# mx8m_phy.net
KiCad netlist of a schematic drawn in Altium Designer
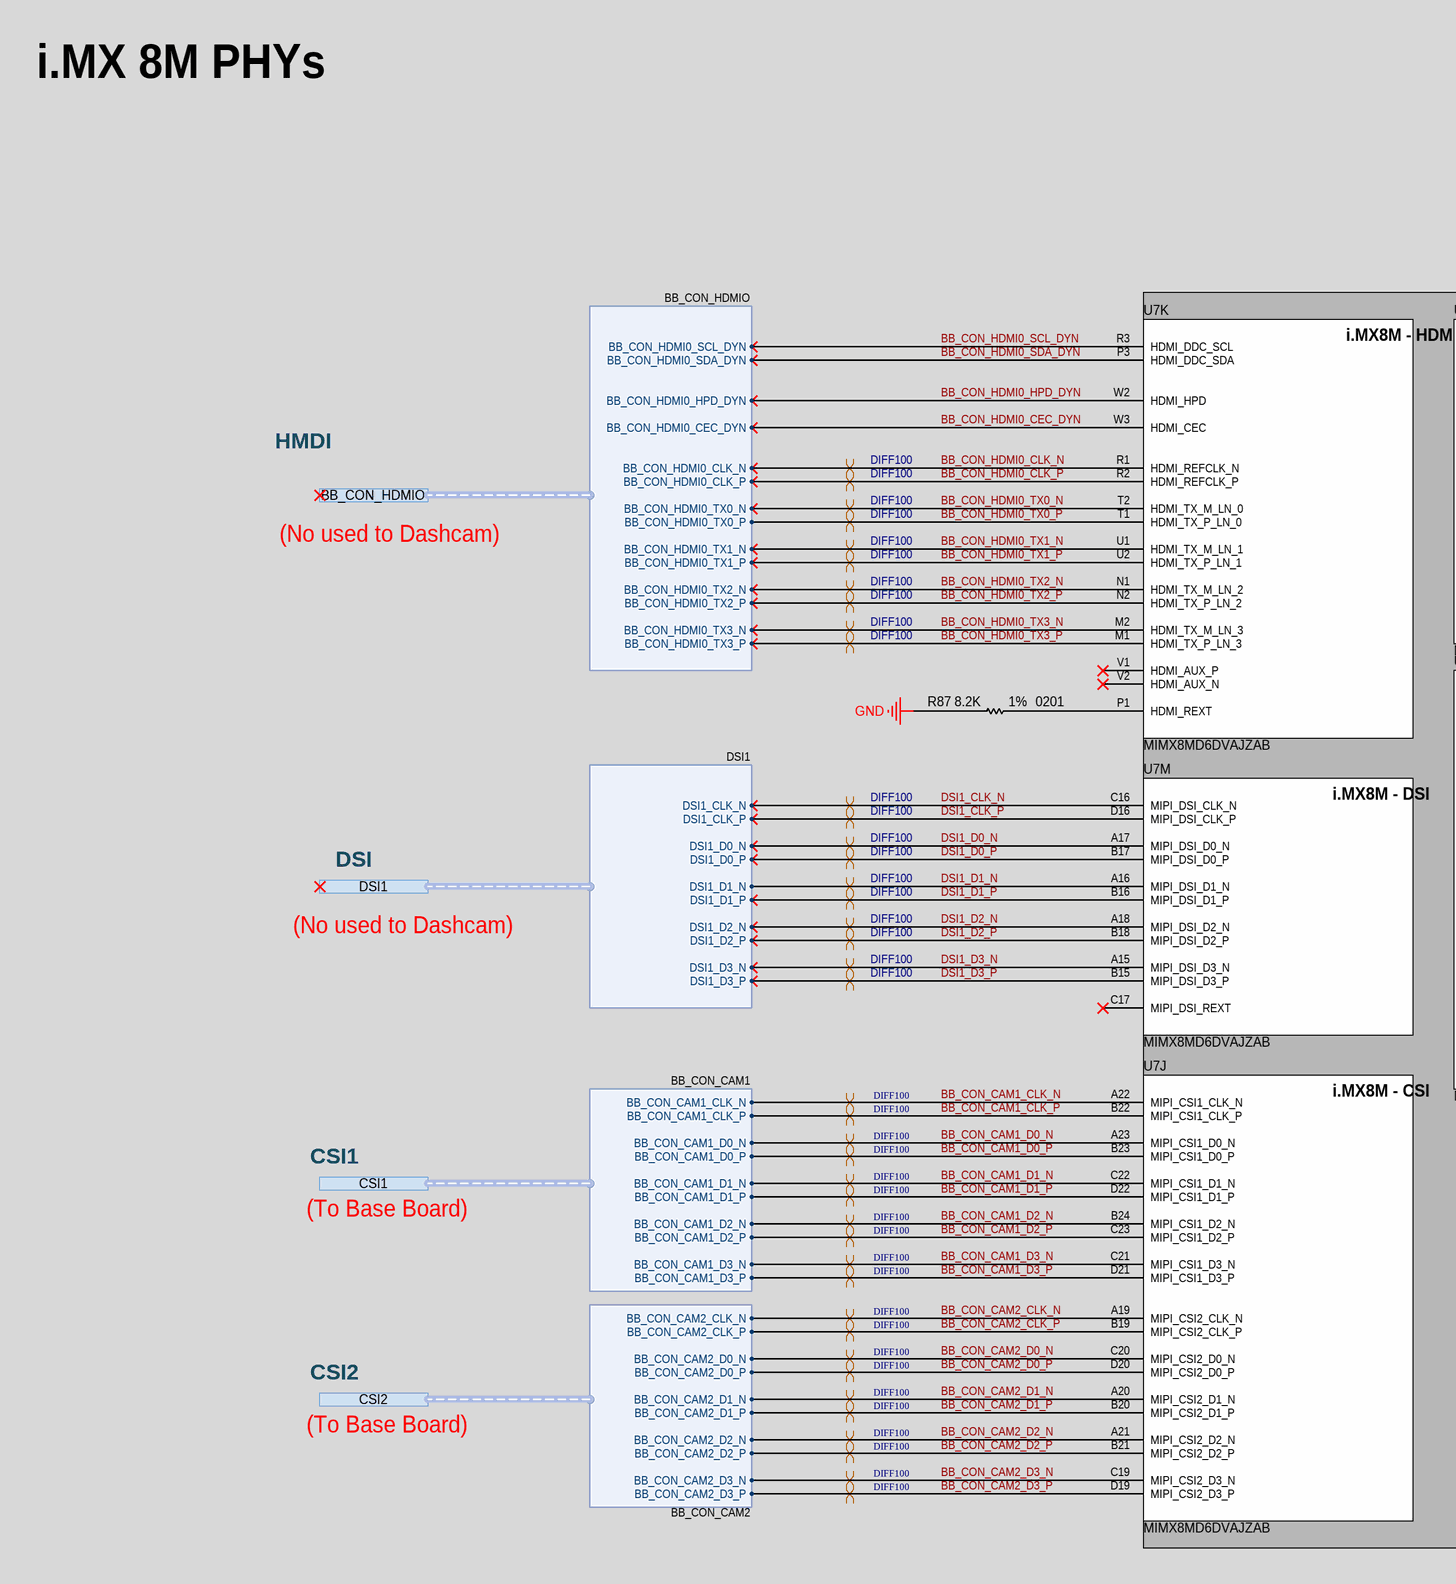
[diagram p0: mx8m_phy.SchDoc, left]
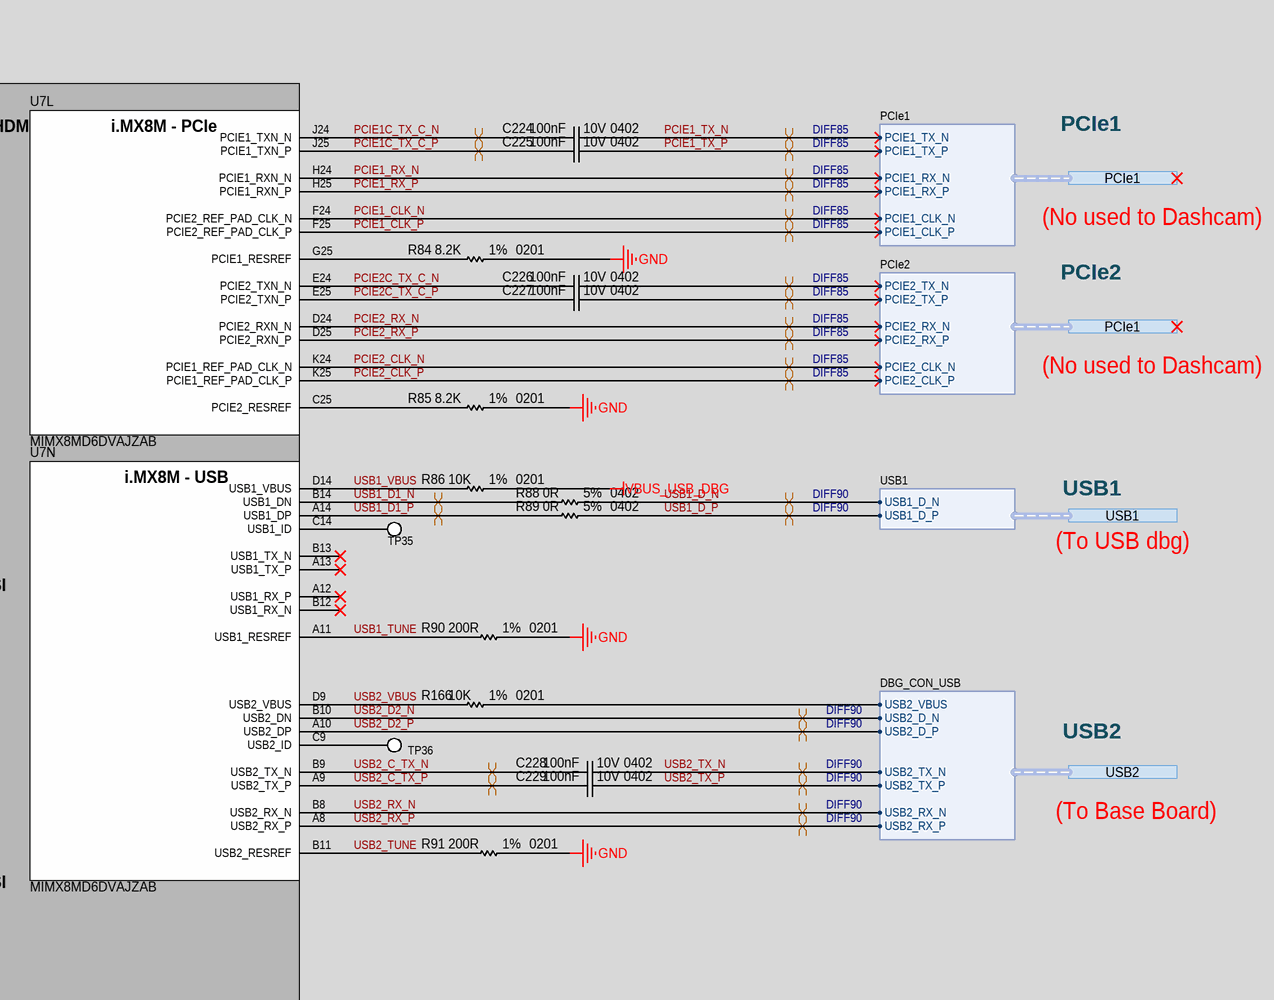
[diagram p1: mx8m_phy.SchDoc, right]

(export (version "E")
  (design (tool "Eeschema 10.0.6"))
  (components
    (comp (ref "C224")
      (value "GRM155R61A104KA01D")
      (footprint "CAP_0402_CAPC1005X05N")
      (description "Multilayer Ceramic Capacitor, 0.1 uF, 10 V, ± 10%, X5R, 0402 [1005 Metric]")
      (fields
        (field (name "MANUFACTURER") "Murata")
        (field (name "TOLERANCE") "10%")
        (field (name "CASE CODE (IMPERIAL)") "0402")
        (field (name "VOLTAGE RATING (DC)") "10V")
        (field (name "CAPACITANCE") "100nF")
      )
      (libsource (lib "Electronic Devices_LIB") (part "CAP_100nF_10V_X5R_0402"))
    )
    (comp (ref "C225")
      (value "GRM155R61A104KA01D")
      (footprint "CAP_0402_CAPC1005X05N")
      (description "Multilayer Ceramic Capacitor, 0.1 uF, 10 V, ± 10%, X5R, 0402 [1005 Metric]")
      (fields
        (field (name "MANUFACTURER") "Murata")
        (field (name "TOLERANCE") "10%")
        (field (name "CASE CODE (IMPERIAL)") "0402")
        (field (name "VOLTAGE RATING (DC)") "10V")
        (field (name "CAPACITANCE") "100nF")
      )
      (libsource (lib "Electronic Devices_LIB") (part "CAP_100nF_10V_X5R_0402"))
    )
    (comp (ref "C226")
      (value "GRM155R61A104KA01D")
      (footprint "CAP_0402_CAPC1005X05N")
      (description "Multilayer Ceramic Capacitor, 0.1 uF, 10 V, ± 10%, X5R, 0402 [1005 Metric]")
      (fields
        (field (name "MANUFACTURER") "Murata")
        (field (name "TOLERANCE") "10%")
        (field (name "CASE CODE (IMPERIAL)") "0402")
        (field (name "VOLTAGE RATING (DC)") "10V")
        (field (name "CAPACITANCE") "100nF")
      )
      (libsource (lib "Electronic Devices_LIB") (part "CAP_100nF_10V_X5R_0402"))
    )
    (comp (ref "C227")
      (value "GRM155R61A104KA01D")
      (footprint "CAP_0402_CAPC1005X05N")
      (description "Multilayer Ceramic Capacitor, 0.1 uF, 10 V, ± 10%, X5R, 0402 [1005 Metric]")
      (fields
        (field (name "MANUFACTURER") "Murata")
        (field (name "TOLERANCE") "10%")
        (field (name "CASE CODE (IMPERIAL)") "0402")
        (field (name "VOLTAGE RATING (DC)") "10V")
        (field (name "CAPACITANCE") "100nF")
      )
      (libsource (lib "Electronic Devices_LIB") (part "CAP_100nF_10V_X5R_0402"))
    )
    (comp (ref "C228")
      (value "GRM155R61A104KA01D")
      (footprint "CAP_0402_CAPC1005X05N")
      (description "Multilayer Ceramic Capacitor, 0.1 uF, 10 V, ± 10%, X5R, 0402 [1005 Metric]")
      (fields
        (field (name "MANUFACTURER") "Murata")
        (field (name "TOLERANCE") "10%")
        (field (name "CASE CODE (IMPERIAL)") "0402")
        (field (name "VOLTAGE RATING (DC)") "10V")
        (field (name "CAPACITANCE") "100nF")
      )
      (libsource (lib "Electronic Devices_LIB") (part "CAP_100nF_10V_X5R_0402"))
    )
    (comp (ref "C229")
      (value "GRM155R61A104KA01D")
      (footprint "CAP_0402_CAPC1005X05N")
      (description "Multilayer Ceramic Capacitor, 0.1 uF, 10 V, ± 10%, X5R, 0402 [1005 Metric]")
      (fields
        (field (name "MANUFACTURER") "Murata")
        (field (name "TOLERANCE") "10%")
        (field (name "CASE CODE (IMPERIAL)") "0402")
        (field (name "VOLTAGE RATING (DC)") "10V")
        (field (name "CAPACITANCE") "100nF")
      )
      (libsource (lib "Electronic Devices_LIB") (part "CAP_100nF_10V_X5R_0402"))
    )
    (comp (ref "R84")
      (value "RC0201FR-078K2L")
      (footprint "RES_0201_RESC0603X02N")
      (description "Res Thick Film 0201 8.2K Ohm 1% 1/20W ±200ppm/°C Molded SMD Paper T/R")
      (fields
        (field (name "MANUFACTURER") "Yageo")
        (field (name "TOLERANCE") "1%")
        (field (name "RESISTANCE") "8.2K")
        (field (name "CASE/PACKAGE") "0201")
      )
      (libsource (lib "Electronic Devices_LIB") (part "RES_8.2K_1%_50mW_0201"))
    )
    (comp (ref "R85")
      (value "RC0201FR-078K2L")
      (footprint "RES_0201_RESC0603X02N")
      (description "Res Thick Film 0201 8.2K Ohm 1% 1/20W ±200ppm/°C Molded SMD Paper T/R")
      (fields
        (field (name "MANUFACTURER") "Yageo")
        (field (name "TOLERANCE") "1%")
        (field (name "RESISTANCE") "8.2K")
        (field (name "CASE/PACKAGE") "0201")
      )
      (libsource (lib "Electronic Devices_LIB") (part "RES_8.2K_1%_50mW_0201"))
    )
    (comp (ref "R86")
      (value "RC0201FR-0710KL")
      (footprint "RES_0201_RESC0603X02N")
      (description "SMD Chip Resistor, 10 kOhm, ± 1%, 50 mW, 0201 [0603 Metric], Thick Film, General Purpose")
      (fields
        (field (name "MANUFACTURER") "Yageo")
        (field (name "TOLERANCE") "1%")
        (field (name "RESISTANCE") "10K")
        (field (name "CASE CODE (IMPERIAL)") "0201")
      )
      (libsource (lib "Electronic Devices_LIB") (part "RES_10K_1/12W_1%_0201"))
    )
    (comp (ref "R87")
      (value "RC0201FR-078K2L")
      (footprint "RES_0201_RESC0603X02N")
      (description "Res Thick Film 0201 8.2K Ohm 1% 1/20W ±200ppm/°C Molded SMD Paper T/R")
      (fields
        (field (name "MANUFACTURER") "Yageo")
        (field (name "TOLERANCE") "1%")
        (field (name "RESISTANCE") "8.2K")
        (field (name "CASE/PACKAGE") "0201")
      )
      (libsource (lib "Electronic Devices_LIB") (part "RES_8.2K_1%_50mW_0201"))
    )
    (comp (ref "R88")
      (value "ERJ-2GE0R00X")
      (footprint "RES_0402_RESC1005X04N")
      (description "SMD Chip Resistor, Jumper, 0 ohm, 100 mW, 0402 [1005 Metric], Thick Film, General Purpose")
      (fields
        (field (name "MANUFACTURER") "Panasonic")
        (field (name "CASE CODE (IMPERIAL)") "0402")
        (field (name "TOLERANCE") "5%")
        (field (name "RESISTANCE") "0R")
      )
      (libsource (lib "Electronic Devices_LIB") (part "RES_0R_5%_100mW_0402"))
    )
    (comp (ref "R89")
      (value "ERJ-2GE0R00X")
      (footprint "RES_0402_RESC1005X04N")
      (description "SMD Chip Resistor, Jumper, 0 ohm, 100 mW, 0402 [1005 Metric], Thick Film, General Purpose")
      (fields
        (field (name "MANUFACTURER") "Panasonic")
        (field (name "CASE CODE (IMPERIAL)") "0402")
        (field (name "TOLERANCE") "5%")
        (field (name "RESISTANCE") "0R")
      )
      (libsource (lib "Electronic Devices_LIB") (part "RES_0R_5%_100mW_0402"))
    )
    (comp (ref "R90")
      (value "RC0201FR-07200RL")
      (footprint "RES_0201_RESC0603X02N")
      (description "SMD Chip Resistor, 200 Ohm, ± 1%, 50 mW, 0201 [0603 Metric], Thick Film, General Purpose")
      (fields
        (field (name "MANUFACTURER") "Yageo")
        (field (name "TOLERANCE") "1%")
        (field (name "RESISTANCE") "200R")
        (field (name "CASE/PACKAGE") "0201")
      )
      (libsource (lib "Electronic Devices_LIB") (part "RES_200R_1%_50mW_0201"))
    )
    (comp (ref "R91")
      (value "RC0201FR-07200RL")
      (footprint "RES_0201_RESC0603X02N")
      (description "SMD Chip Resistor, 200 Ohm, ± 1%, 50 mW, 0201 [0603 Metric], Thick Film, General Purpose")
      (fields
        (field (name "MANUFACTURER") "Yageo")
        (field (name "TOLERANCE") "1%")
        (field (name "RESISTANCE") "200R")
        (field (name "CASE/PACKAGE") "0201")
      )
      (libsource (lib "Electronic Devices_LIB") (part "RES_200R_1%_50mW_0201"))
    )
    (comp (ref "R166")
      (value "RC0201FR-0710KL")
      (footprint "RES_0201_RESC0603X02N")
      (description "SMD Chip Resistor, 10 kOhm, ± 1%, 50 mW, 0201 [0603 Metric], Thick Film, General Purpose")
      (fields
        (field (name "MANUFACTURER") "Yageo")
        (field (name "TOLERANCE") "1%")
        (field (name "RESISTANCE") "10K")
        (field (name "CASE CODE (IMPERIAL)") "0201")
      )
      (libsource (lib "Electronic Devices_LIB") (part "RES_10K_1/12W_1%_0201"))
    )
    (comp (ref "TP35")
      (value "NO COMPONENT")
      (footprint "TP_PAD_1.6MM_SMD_ROUND")
      (description "Test Point, SMD pad, round, 1.5mm, 1.6mm, 3mm diameter")
      (libsource (lib "Electronic Devices_LIB") (part "TP_PAD_SMD_Round"))
    )
    (comp (ref "TP36")
      (value "NO COMPONENT")
      (footprint "TP_PAD_1.6MM_SMD_ROUND")
      (description "Test Point, SMD pad, round, 1.5mm, 1.6mm, 3mm diameter")
      (libsource (lib "Electronic Devices_LIB") (part "TP_PAD_SMD_Round"))
    )
    (comp (ref "U7")
      (value "MIMX8MD6DVAJZAB")
      (footprint "IC_MPU_BGA621C65P25X25_1700X1700X218")
      (fields (field (name "MANUFACTURER") "NXP Semiconductors"))
      (libsource (lib "Electronic Devices_LIB") (part "IC_MPU_ARM_1.5GHZ_MIMX8MD6DVAJZAB"))
    )
  )
  (nets
    (net (code "9") (name "/BB_CON_CAM1_CLK_N") (class "Default")
      (node (ref "U7") (pin "A22") (pinfunction "MIPI_CSI1_CLK_N_A22") (pintype "passive"))
    )
    (net (code "10") (name "/BB_CON_CAM1_CLK_P") (class "Default")
      (node (ref "U7") (pin "B22") (pinfunction "MIPI_CSI1_CLK_P_B22") (pintype "passive"))
    )
    (net (code "11") (name "/BB_CON_CAM1_D0_N") (class "Default")
      (node (ref "U7") (pin "A23") (pinfunction "MIPI_CSI1_D0_N_A23") (pintype "passive"))
    )
    (net (code "12") (name "/BB_CON_CAM1_D0_P") (class "Default")
      (node (ref "U7") (pin "B23") (pinfunction "MIPI_CSI1_D0_P_B23") (pintype "passive"))
    )
    (net (code "13") (name "/BB_CON_CAM1_D1_N") (class "Default")
      (node (ref "U7") (pin "C22") (pinfunction "MIPI_CSI1_D1_N_C22") (pintype "passive"))
    )
    (net (code "14") (name "/BB_CON_CAM1_D1_P") (class "Default")
      (node (ref "U7") (pin "D22") (pinfunction "MIPI_CSI1_D1_P_D22") (pintype "passive"))
    )
    (net (code "15") (name "/BB_CON_CAM1_D2_N") (class "Default")
      (node (ref "U7") (pin "B24") (pinfunction "MIPI_CSI1_D2_N_B24") (pintype "passive"))
    )
    (net (code "16") (name "/BB_CON_CAM1_D2_P") (class "Default")
      (node (ref "U7") (pin "C23") (pinfunction "MIPI_CSI1_D2_P_C23") (pintype "passive"))
    )
    (net (code "17") (name "/BB_CON_CAM1_D3_N") (class "Default")
      (node (ref "U7") (pin "C21") (pinfunction "MIPI_CSI1_D3_N_C21") (pintype "passive"))
    )
    (net (code "18") (name "/BB_CON_CAM1_D3_P") (class "Default")
      (node (ref "U7") (pin "D21") (pinfunction "MIPI_CSI1_D3_P_D21") (pintype "passive"))
    )
    (net (code "19") (name "/BB_CON_CAM2_CLK_N") (class "Default")
      (node (ref "U7") (pin "A19") (pinfunction "MIPI_CSI2_CLK_N_A19") (pintype "passive"))
    )
    (net (code "20") (name "/BB_CON_CAM2_CLK_P") (class "Default")
      (node (ref "U7") (pin "B19") (pinfunction "MIPI_CSI2_CLK_P_B19") (pintype "passive"))
    )
    (net (code "21") (name "/BB_CON_CAM2_D0_N") (class "Default")
      (node (ref "U7") (pin "C20") (pinfunction "MIPI_CSI2_D0_N_C20") (pintype "passive"))
    )
    (net (code "22") (name "/BB_CON_CAM2_D0_P") (class "Default")
      (node (ref "U7") (pin "D20") (pinfunction "MIPI_CSI2_D0_P_D20") (pintype "passive"))
    )
    (net (code "23") (name "/BB_CON_CAM2_D1_N") (class "Default")
      (node (ref "U7") (pin "A20") (pinfunction "MIPI_CSI2_D1_N_A20") (pintype "passive"))
    )
    (net (code "24") (name "/BB_CON_CAM2_D1_P") (class "Default")
      (node (ref "U7") (pin "B20") (pinfunction "MIPI_CSI2_D1_P_B20") (pintype "passive"))
    )
    (net (code "25") (name "/BB_CON_CAM2_D2_N") (class "Default")
      (node (ref "U7") (pin "A21") (pinfunction "MIPI_CSI2_D2_N_A21") (pintype "passive"))
    )
    (net (code "26") (name "/BB_CON_CAM2_D2_P") (class "Default")
      (node (ref "U7") (pin "B21") (pinfunction "MIPI_CSI2_D2_P_B21") (pintype "passive"))
    )
    (net (code "27") (name "/BB_CON_CAM2_D3_N") (class "Default")
      (node (ref "U7") (pin "C19") (pinfunction "MIPI_CSI2_D3_N_C19") (pintype "passive"))
    )
    (net (code "28") (name "/BB_CON_CAM2_D3_P") (class "Default")
      (node (ref "U7") (pin "D19") (pinfunction "MIPI_CSI2_D3_P_D19") (pintype "passive"))
    )
    (net (code "29") (name "/BB_CON_HDMI0_CEC_DYN") (class "Default")
      (node (ref "U7") (pin "W3") (pinfunction "HDMI_CEC_W3") (pintype "passive+no_connect"))
    )
    (net (code "30") (name "/BB_CON_HDMI0_CLK_N") (class "Default")
      (node (ref "U7") (pin "R1") (pinfunction "HDMI_REFCLK_N_R1") (pintype "passive+no_connect"))
    )
    (net (code "31") (name "/BB_CON_HDMI0_CLK_P") (class "Default")
      (node (ref "U7") (pin "R2") (pinfunction "HDMI_REFCLK_P_R2") (pintype "passive+no_connect"))
    )
    (net (code "32") (name "/BB_CON_HDMI0_HPD_DYN") (class "Default")
      (node (ref "U7") (pin "W2") (pinfunction "HDMI_HPD_W2") (pintype "passive+no_connect"))
    )
    (net (code "33") (name "/BB_CON_HDMI0_SCL_DYN") (class "Default")
      (node (ref "U7") (pin "R3") (pinfunction "HDMI_DDC_SCL_R3") (pintype "passive+no_connect"))
    )
    (net (code "34") (name "/BB_CON_HDMI0_SDA_DYN") (class "Default")
      (node (ref "U7") (pin "P3") (pinfunction "HDMI_DDC_SDA_P3") (pintype "passive+no_connect"))
    )
    (net (code "35") (name "/BB_CON_HDMI0_TX0_N") (class "Default")
      (node (ref "U7") (pin "T2") (pinfunction "HDMI_TX_M_LN_0_T2") (pintype "passive+no_connect"))
    )
    (net (code "36") (name "/BB_CON_HDMI0_TX0_P") (class "Default")
      (node (ref "U7") (pin "T1") (pinfunction "HDMI_TX_P_LN_0_T1") (pintype "passive"))
    )
    (net (code "37") (name "/BB_CON_HDMI0_TX1_N") (class "Default")
      (node (ref "U7") (pin "U1") (pinfunction "HDMI_TX_M_LN_1_U1") (pintype "passive+no_connect"))
    )
    (net (code "38") (name "/BB_CON_HDMI0_TX1_P") (class "Default")
      (node (ref "U7") (pin "U2") (pinfunction "HDMI_TX_P_LN_1_U2") (pintype "passive+no_connect"))
    )
    (net (code "39") (name "/BB_CON_HDMI0_TX2_N") (class "Default")
      (node (ref "U7") (pin "N1") (pinfunction "HDMI_TX_M_LN_2_N1") (pintype "passive+no_connect"))
    )
    (net (code "40") (name "/BB_CON_HDMI0_TX2_P") (class "Default")
      (node (ref "U7") (pin "N2") (pinfunction "HDMI_TX_P_LN_2_N2") (pintype "passive+no_connect"))
    )
    (net (code "41") (name "/BB_CON_HDMI0_TX3_N") (class "Default")
      (node (ref "U7") (pin "M2") (pinfunction "HDMI_TX_M_LN_3_M2") (pintype "passive+no_connect"))
    )
    (net (code "42") (name "/BB_CON_HDMI0_TX3_P") (class "Default")
      (node (ref "U7") (pin "M1") (pinfunction "HDMI_TX_P_LN_3_M1") (pintype "passive+no_connect"))
    )
    (net (code "43") (name "/DSI1_CLK_N") (class "Default")
      (node (ref "U7") (pin "C16") (pinfunction "MIPI_DSI_CLK_N_C16") (pintype "passive+no_connect"))
    )
    (net (code "44") (name "/DSI1_CLK_P") (class "Default")
      (node (ref "U7") (pin "D16") (pinfunction "MIPI_DSI_CLK_P_D16") (pintype "passive+no_connect"))
    )
    (net (code "45") (name "/DSI1_D0_N") (class "Default")
      (node (ref "U7") (pin "A17") (pinfunction "MIPI_DSI_D0_N_A17") (pintype "passive+no_connect"))
    )
    (net (code "46") (name "/DSI1_D0_P") (class "Default")
      (node (ref "U7") (pin "B17") (pinfunction "MIPI_DSI_D0_P_B17") (pintype "passive+no_connect"))
    )
    (net (code "47") (name "/DSI1_D1_N") (class "Default")
      (node (ref "U7") (pin "A16") (pinfunction "MIPI_DSI_D1_N_A16") (pintype "passive"))
    )
    (net (code "48") (name "/DSI1_D1_P") (class "Default")
      (node (ref "U7") (pin "B16") (pinfunction "MIPI_DSI_D1_P_B16") (pintype "passive+no_connect"))
    )
    (net (code "49") (name "/DSI1_D2_N") (class "Default")
      (node (ref "U7") (pin "A18") (pinfunction "MIPI_DSI_D2_N_A18") (pintype "passive+no_connect"))
    )
    (net (code "50") (name "/DSI1_D2_P") (class "Default")
      (node (ref "U7") (pin "B18") (pinfunction "MIPI_DSI_D2_P_B18") (pintype "passive+no_connect"))
    )
    (net (code "51") (name "/DSI1_D3_N") (class "Default")
      (node (ref "U7") (pin "A15") (pinfunction "MIPI_DSI_D3_N_A15") (pintype "passive+no_connect"))
    )
    (net (code "52") (name "/DSI1_D3_P") (class "Default")
      (node (ref "U7") (pin "B15") (pinfunction "MIPI_DSI_D3_P_B15") (pintype "passive+no_connect"))
    )
    (net (code "53") (name "/PCIE1C_TX_C_N") (class "Default")
      (node (ref "C224") (pin "1") (pinfunction "1_1") (pintype "passive"))
      (node (ref "U7") (pin "J24") (pinfunction "PCIE1_TXN_N_J24") (pintype "passive"))
    )
    (net (code "54") (name "/PCIE1C_TX_C_P") (class "Default")
      (node (ref "C225") (pin "1") (pinfunction "1_1") (pintype "passive"))
      (node (ref "U7") (pin "J25") (pinfunction "PCIE1_TXN_P_J25") (pintype "passive"))
    )
    (net (code "55") (name "/PCIE1_CLK_N") (class "Default")
      (node (ref "U7") (pin "F24") (pinfunction "PCIE2_REF_PAD_CLK_N_F24") (pintype "passive+no_connect"))
    )
    (net (code "56") (name "/PCIE1_CLK_P") (class "Default")
      (node (ref "U7") (pin "F25") (pinfunction "PCIE2_REF_PAD_CLK_P_F25") (pintype "passive+no_connect"))
    )
    (net (code "57") (name "/PCIE1_RX_N") (class "Default")
      (node (ref "U7") (pin "H24") (pinfunction "PCIE1_RXN_N_H24") (pintype "passive+no_connect"))
    )
    (net (code "58") (name "/PCIE1_RX_P") (class "Default")
      (node (ref "U7") (pin "H25") (pinfunction "PCIE1_RXN_P_H25") (pintype "passive+no_connect"))
    )
    (net (code "59") (name "/PCIE1_TX_N") (class "Default")
      (node (ref "C224") (pin "2") (pinfunction "2_2") (pintype "passive+no_connect"))
    )
    (net (code "60") (name "/PCIE1_TX_P") (class "Default")
      (node (ref "C225") (pin "2") (pinfunction "2_2") (pintype "passive+no_connect"))
    )
    (net (code "61") (name "/PCIE2C_TX_C_N") (class "Default")
      (node (ref "C226") (pin "1") (pinfunction "1_1") (pintype "passive"))
      (node (ref "U7") (pin "E24") (pinfunction "PCIE2_TXN_N_E24") (pintype "passive"))
    )
    (net (code "62") (name "/PCIE2C_TX_C_P") (class "Default")
      (node (ref "C227") (pin "1") (pinfunction "1_1") (pintype "passive"))
      (node (ref "U7") (pin "E25") (pinfunction "PCIE2_TXN_P_E25") (pintype "passive"))
    )
    (net (code "63") (name "/PCIE2_CLK_N") (class "Default")
      (node (ref "U7") (pin "K24") (pinfunction "PCIE1_REF_PAD_CLK_N_K24") (pintype "passive+no_connect"))
    )
    (net (code "64") (name "/PCIE2_CLK_P") (class "Default")
      (node (ref "U7") (pin "K25") (pinfunction "PCIE1_REF_PAD_CLK_P_K25") (pintype "passive+no_connect"))
    )
    (net (code "65") (name "/PCIE2_RX_N") (class "Default")
      (node (ref "U7") (pin "D24") (pinfunction "PCIE2_RXN_N_D24") (pintype "passive+no_connect"))
    )
    (net (code "66") (name "/PCIE2_RX_P") (class "Default")
      (node (ref "U7") (pin "D25") (pinfunction "PCIE2_RXN_P_D25") (pintype "passive+no_connect"))
    )
    (net (code "67") (name "/PCIE2_TX_N") (class "Default")
      (node (ref "C226") (pin "2") (pinfunction "2_2") (pintype "passive+no_connect"))
    )
    (net (code "68") (name "/PCIE2_TX_P") (class "Default")
      (node (ref "C227") (pin "2") (pinfunction "2_2") (pintype "passive+no_connect"))
    )
    (net (code "69") (name "/USB1_D1_N") (class "Default")
      (node (ref "R88") (pin "1") (pinfunction "1_1") (pintype "passive"))
      (node (ref "U7") (pin "B14") (pinfunction "USB1_DN_B14") (pintype "passive"))
    )
    (net (code "70") (name "/USB1_D1_P") (class "Default")
      (node (ref "R89") (pin "1") (pinfunction "1_1") (pintype "passive"))
      (node (ref "U7") (pin "A14") (pinfunction "USB1_DP_A14") (pintype "passive"))
    )
    (net (code "71") (name "/USB1_D_N") (class "Default")
      (node (ref "R88") (pin "2") (pinfunction "2_2") (pintype "passive"))
    )
    (net (code "72") (name "/USB1_D_P") (class "Default")
      (node (ref "R89") (pin "2") (pinfunction "2_2") (pintype "passive"))
    )
    (net (code "73") (name "/USB1_TUNE") (class "Default")
      (node (ref "R90") (pin "1") (pinfunction "1_1") (pintype "passive"))
      (node (ref "U7") (pin "A11") (pinfunction "USB1_RESREF_A11") (pintype "passive"))
    )
    (net (code "74") (name "/USB1_VBUS") (class "Default")
      (node (ref "R86") (pin "1") (pinfunction "1_1") (pintype "passive"))
      (node (ref "U7") (pin "D14") (pinfunction "USB1_VBUS_D14") (pintype "passive"))
    )
    (net (code "75") (name "/USB2_C_TX_N") (class "Default")
      (node (ref "C228") (pin "1") (pinfunction "1_1") (pintype "passive"))
      (node (ref "U7") (pin "B9") (pinfunction "USB2_TX_N_B9") (pintype "passive"))
    )
    (net (code "76") (name "/USB2_C_TX_P") (class "Default")
      (node (ref "C229") (pin "1") (pinfunction "1_1") (pintype "passive"))
      (node (ref "U7") (pin "A9") (pinfunction "USB2_TX_P_A9") (pintype "passive"))
    )
    (net (code "77") (name "/USB2_D2_N") (class "Default")
      (node (ref "U7") (pin "B10") (pinfunction "USB2_DN_B10") (pintype "passive"))
    )
    (net (code "78") (name "/USB2_D2_P") (class "Default")
      (node (ref "U7") (pin "A10") (pinfunction "USB2_DP_A10") (pintype "passive"))
    )
    (net (code "79") (name "/USB2_RX_N") (class "Default")
      (node (ref "U7") (pin "B8") (pinfunction "USB2_RX_N_B8") (pintype "passive"))
    )
    (net (code "80") (name "/USB2_RX_P") (class "Default")
      (node (ref "U7") (pin "A8") (pinfunction "USB2_RX_P_A8") (pintype "passive"))
    )
    (net (code "81") (name "/USB2_TUNE") (class "Default")
      (node (ref "R91") (pin "1") (pinfunction "1_1") (pintype "passive"))
      (node (ref "U7") (pin "B11") (pinfunction "USB2_RESREF_B11") (pintype "passive"))
    )
    (net (code "82") (name "/USB2_TX_N") (class "Default")
      (node (ref "C228") (pin "2") (pinfunction "2_2") (pintype "passive"))
    )
    (net (code "83") (name "/USB2_TX_P") (class "Default")
      (node (ref "C229") (pin "2") (pinfunction "2_2") (pintype "passive"))
    )
    (net (code "84") (name "/USB2_VBUS") (class "Default")
      (node (ref "R166") (pin "1") (pinfunction "1_1") (pintype "passive"))
      (node (ref "U7") (pin "D9") (pinfunction "USB2_VBUS_D9") (pintype "passive"))
    )
    (net (code "93") (name "GND") (class "Default")
      (node (ref "R84") (pin "2") (pinfunction "2_2") (pintype "passive"))
      (node (ref "R85") (pin "2") (pinfunction "2_2") (pintype "passive"))
      (node (ref "R87") (pin "1") (pinfunction "1_1") (pintype "passive"))
      (node (ref "R90") (pin "2") (pinfunction "2_2") (pintype "passive"))
      (node (ref "R91") (pin "2") (pinfunction "2_2") (pintype "passive"))
    )
    (net (code "94") (name "Net-(U7K-HDMI_REXT)") (class "Default")
      (node (ref "R87") (pin "2") (pinfunction "2_2") (pintype "passive"))
      (node (ref "U7") (pin "P1") (pinfunction "HDMI_REXT_P1") (pintype "passive"))
    )
    (net (code "95") (name "Net-(U7L-PCIE1_RESREF)") (class "Default")
      (node (ref "R84") (pin "1") (pinfunction "1_1") (pintype "passive"))
      (node (ref "U7") (pin "G25") (pinfunction "PCIE1_RESREF_G25") (pintype "passive"))
    )
    (net (code "96") (name "Net-(U7L-PCIE2_RESREF)") (class "Default")
      (node (ref "R85") (pin "1") (pinfunction "1_1") (pintype "passive"))
      (node (ref "U7") (pin "C25") (pinfunction "PCIE2_RESREF_C25") (pintype "passive"))
    )
    (net (code "97") (name "Net-(U7N-USB1_ID)") (class "Default")
      (node (ref "TP35") (pin "1") (pinfunction "1_1") (pintype "passive"))
      (node (ref "U7") (pin "C14") (pinfunction "USB1_ID_C14") (pintype "passive"))
    )
    (net (code "98") (name "Net-(U7N-USB2_ID)") (class "Default")
      (node (ref "TP36") (pin "1") (pinfunction "1_1") (pintype "passive"))
      (node (ref "U7") (pin "C9") (pinfunction "USB2_ID_C9") (pintype "passive"))
    )
    (net (code "99") (name "VBUS_USB_DBG") (class "Default")
      (node (ref "R86") (pin "2") (pinfunction "2_2") (pintype "passive"))
    )
    (net (code "100") (name "unconnected-(R166-Pad2)") (class "Default")
      (node (ref "R166") (pin "2") (pinfunction "2_2") (pintype "passive"))
    )
    (net (code "101") (name "unconnected-(U7K-HDMI_AUX_N-PadV2)") (class "Default")
      (node (ref "U7") (pin "V2") (pinfunction "HDMI_AUX_N_V2") (pintype "passive+no_connect"))
    )
    (net (code "102") (name "unconnected-(U7K-HDMI_AUX_P-PadV1)") (class "Default")
      (node (ref "U7") (pin "V1") (pinfunction "HDMI_AUX_P_V1") (pintype "passive+no_connect"))
    )
    (net (code "103") (name "unconnected-(U7M-MIPI_DSI_REXT-PadC17)") (class "Default")
      (node (ref "U7") (pin "C17") (pinfunction "MIPI_DSI_REXT_C17") (pintype "passive+no_connect"))
    )
    (net (code "104") (name "unconnected-(U7N-USB1_RX_N-PadB12)") (class "Default")
      (node (ref "U7") (pin "B12") (pinfunction "USB1_RX_N_B12") (pintype "passive+no_connect"))
    )
    (net (code "105") (name "unconnected-(U7N-USB1_RX_P-PadA12)") (class "Default")
      (node (ref "U7") (pin "A12") (pinfunction "USB1_RX_P_A12") (pintype "passive+no_connect"))
    )
    (net (code "106") (name "unconnected-(U7N-USB1_TX_N-PadB13)") (class "Default")
      (node (ref "U7") (pin "B13") (pinfunction "USB1_TX_N_B13") (pintype "passive+no_connect"))
    )
    (net (code "107") (name "unconnected-(U7N-USB1_TX_P-PadA13)") (class "Default")
      (node (ref "U7") (pin "A13") (pinfunction "USB1_TX_P_A13") (pintype "passive+no_connect"))
    )
  )
)
